# EEM_Connectors.net
KiCad netlist of a schematic drawn in Altium Designer
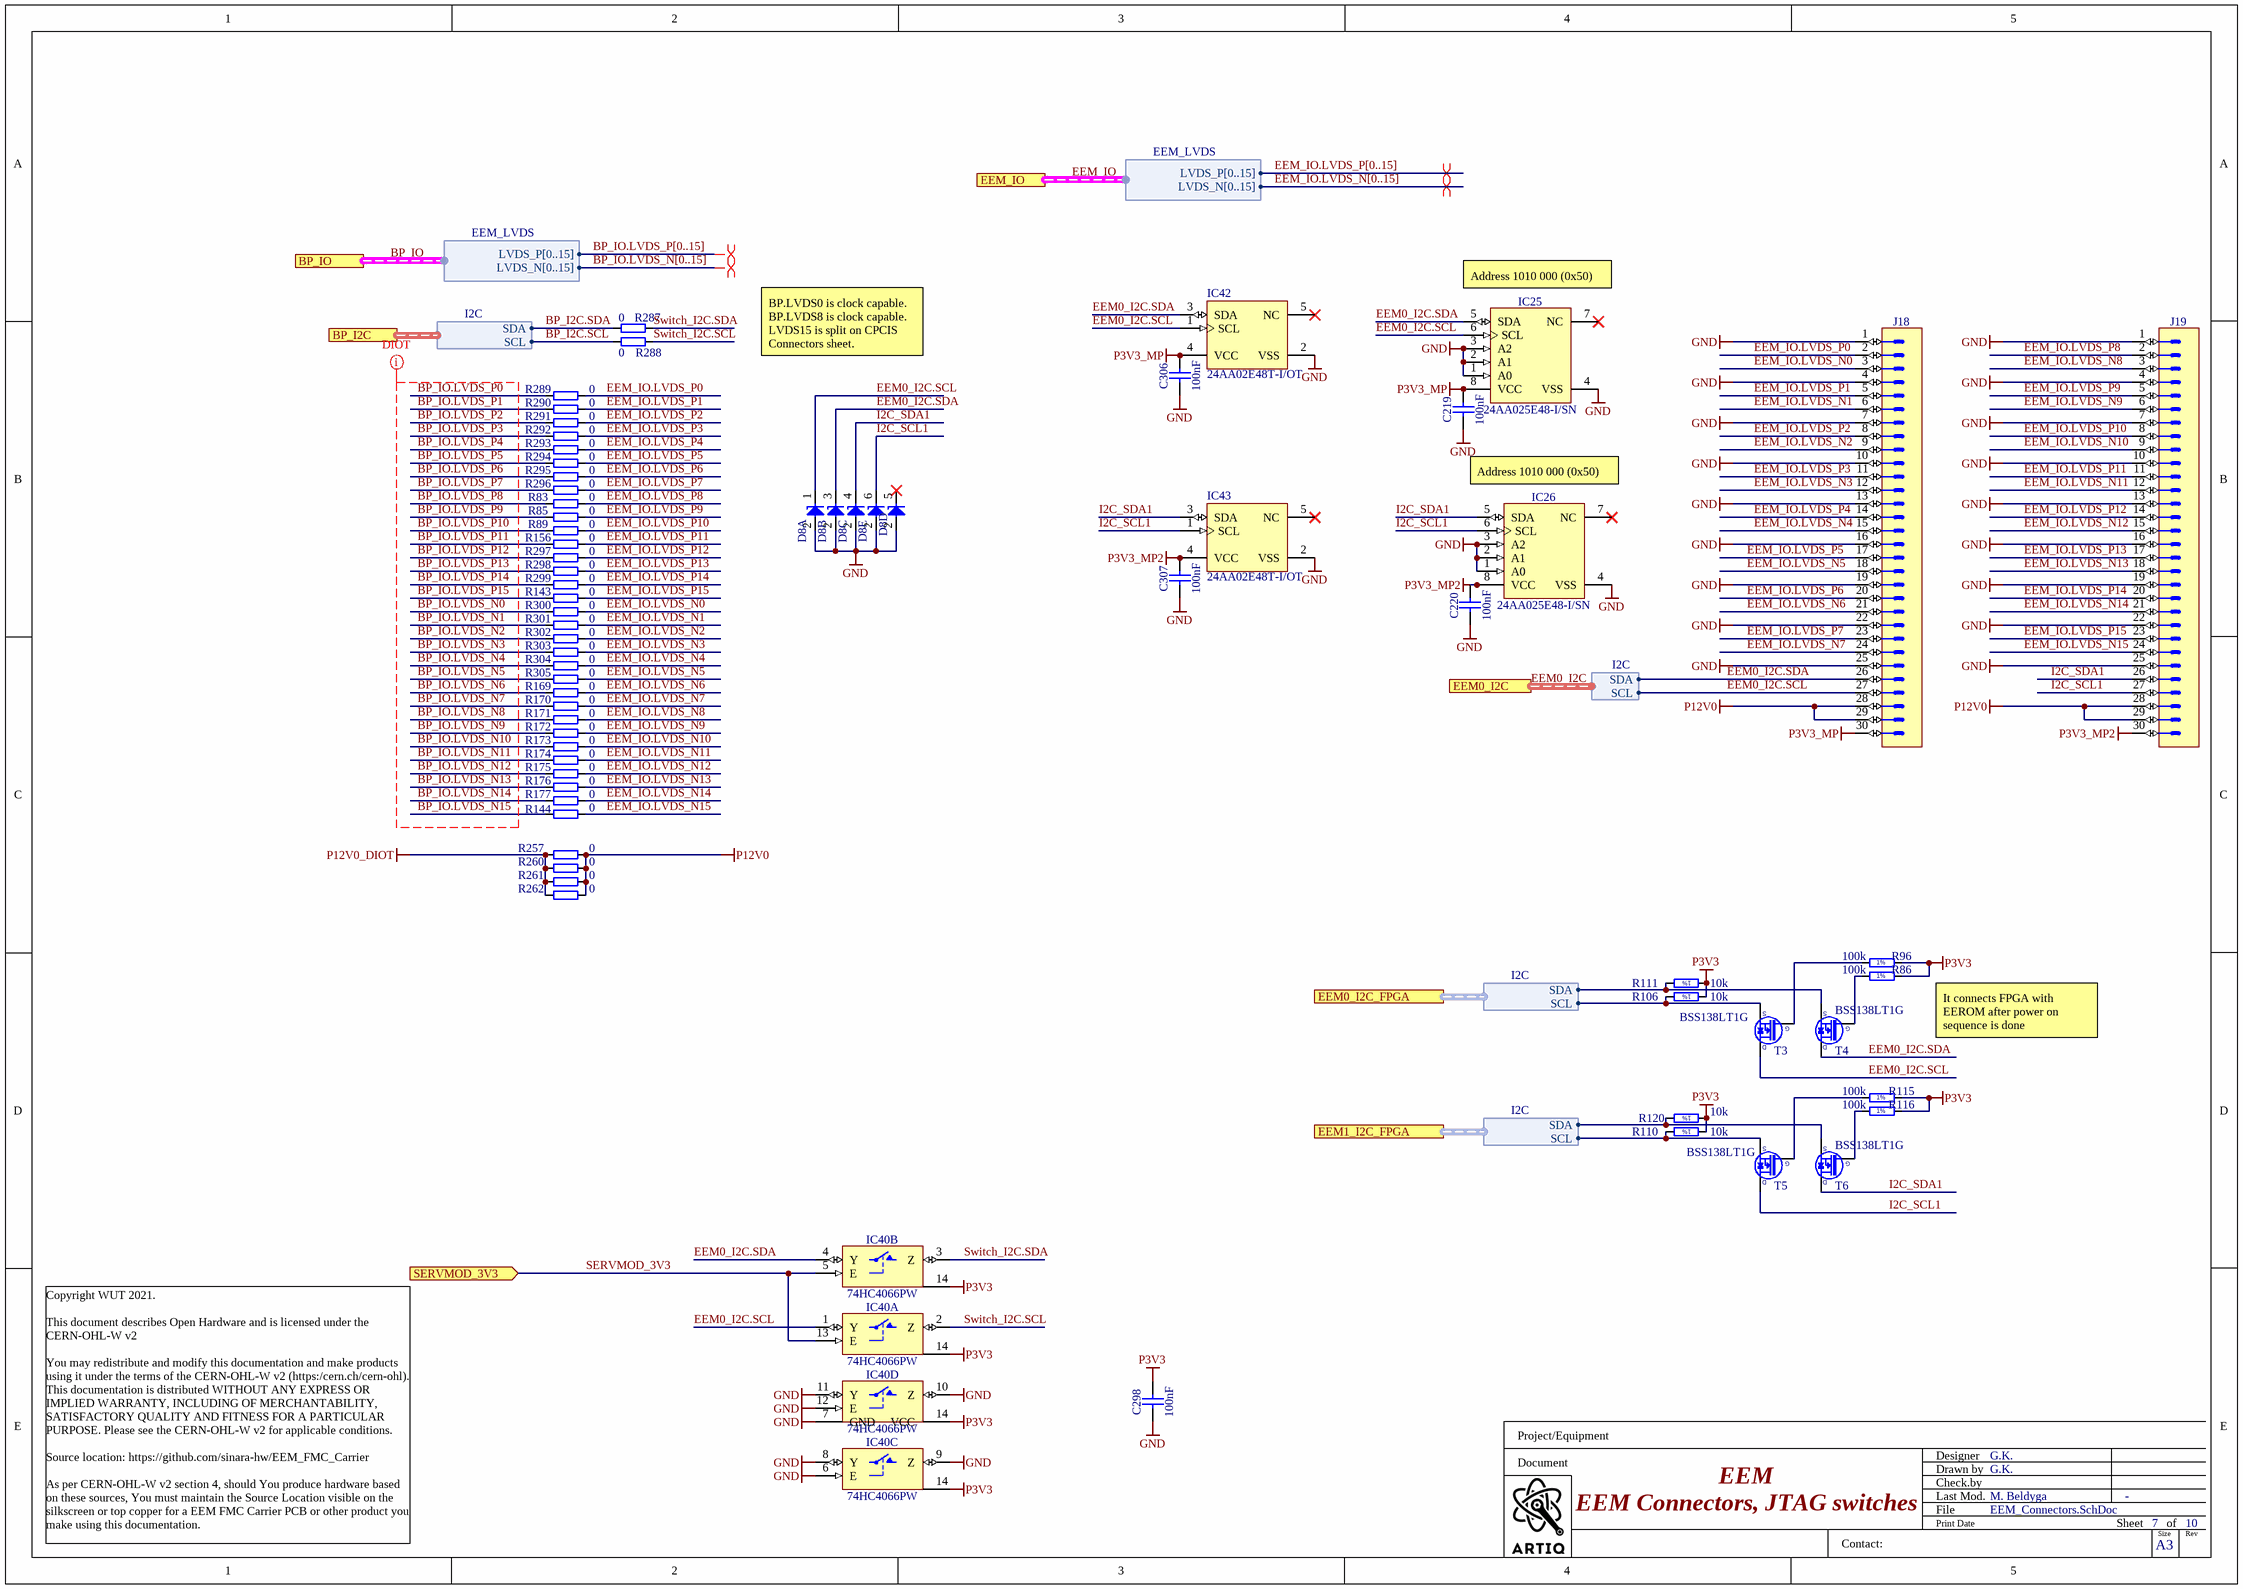
[diagram p0: EEM_Connectors.SchDoc]

(export (version "E")
  (design (tool "Eeschema 10.0.6"))
  (components
    (comp (ref "C219")
      (value "100nF")
      (footprint "CAPC1005X55N")
      (description "Non-polarised capacitor")
      (fields
        (field (name "PART NUMBER") "CC0402_100NF_25V_10%_X7R_YUDEN_TMK105B7104KVHF")
        (field (name "VOLTAGE") "25V")
        (field (name "AUTHOR") "CERN DEM JLC")
      )
      (libsource (lib "Capacitors") (part "Capacitor - non polarized"))
    )
    (comp (ref "C220")
      (value "100nF")
      (footprint "CAPC1005X55N")
      (description "Non-polarised capacitor")
      (fields
        (field (name "PART NUMBER") "CC0402_100NF_16V_10%_X5R")
        (field (name "VOLTAGE") "16V")
        (field (name "AUTHOR") "CERN DEM JLC")
      )
      (libsource (lib "Capacitors") (part "Capacitor - non polarized"))
    )
    (comp (ref "C298")
      (value "100nF")
      (footprint "CAPC1005X55N")
      (description "Non-polarised capacitor")
      (fields
        (field (name "PART NUMBER") "CC0402_100NF_16V_10%_X5R")
        (field (name "VOLTAGE") "16V")
        (field (name "AUTHOR") "CERN DEM JLC")
      )
      (libsource (lib "Capacitors") (part "Capacitor - non polarized"))
    )
    (comp (ref "C306")
      (value "100nF")
      (footprint "CAPC1005X55N")
      (description "Non-polarised capacitor")
      (fields
        (field (name "PART NUMBER") "CC0402_100NF_25V_10%_X7R_YUDEN_TMK105B7104KVHF")
        (field (name "VOLTAGE") "25V")
        (field (name "AUTHOR") "CERN DEM JLC")
      )
      (libsource (lib "Capacitors") (part "Capacitor - non polarized"))
    )
    (comp (ref "C307")
      (value "100nF")
      (footprint "CAPC1005X55N")
      (description "Non-polarised capacitor")
      (fields
        (field (name "PART NUMBER") "CC0402_100NF_25V_10%_X7R_YUDEN_TMK105B7104KVHF")
        (field (name "VOLTAGE") "25V")
        (field (name "AUTHOR") "CERN DEM JLC")
      )
      (libsource (lib "Capacitors") (part "Capacitor - non polarized"))
    )
    (comp (ref "D8")
      (value "PESD3V3L5UY")
      (footprint "SOT65P210X110-6N")
      (description "Fivefold ESD Protection Diode Arrays")
      (fields
        (field (name "VOLTAGE") "3.3V")
        (field (name "POWER") "200W")
        (field (name "AUTHOR") "CERN DEM WB")
      )
      (libsource (lib "ICs And Semiconductors") (part "PESD Array 5diodes 6pins Common anode2"))
    )
    (comp (ref "IC25")
      (value "24AA025E48-I/SN")
      (footprint "SOIC127P600X175-8N")
      (description "1.7V-5.5V, 2K I2C™ Serial EEPROMs with EUI-48™ Node Identity")
      (fields (field (name "MANUFACTURER") "MICROCHIP TECHNOLOGY") (field (name "AUTHOR") "CERN DEM MR"))
      (libsource (lib "ICs And Semiconductors") (part "24AA025E48-I/SN"))
    )
    (comp (ref "IC26")
      (value "24AA025E48-I/SN")
      (footprint "SOIC127P600X175-8N")
      (description "1.7V-5.5V, 2K I2C™ Serial EEPROMs with EUI-48™ Node Identity")
      (fields (field (name "MANUFACTURER") "MICROCHIP TECHNOLOGY") (field (name "AUTHOR") "CERN DEM MR"))
      (libsource (lib "ICs And Semiconductors") (part "24AA025E48-I/SN"))
    )
    (comp (ref "IC40")
      (value "74HC4066PW")
      (footprint "SOP65P640X110-14N")
      (fields (field (name "MANUFACTURER") "NXP SEMICONDUCTORS") (field (name "AUTHOR") "CERN DEM JLC"))
      (libsource (lib "ICs And Semiconductors") (part "4066"))
    )
    (comp (ref "IC42")
      (value "24AA02E48T-I/OT")
      (footprint "SOT95P280X145-5N")
      (description "1.7V-5.5V, 2K I2C Serial EEPROM With EUI-48 Node Identity")
      (fields (field (name "MANUFACTURER") "MICROCHIP TECHNOLOGY") (field (name "AUTHOR") "CERN DEM MR"))
      (libsource (lib "ICs And Semiconductors") (part "24AA02E48T-I/OT"))
    )
    (comp (ref "IC43")
      (value "24AA02E48T-I/OT")
      (footprint "SOT95P280X145-5N")
      (description "1.7V-5.5V, 2K I2C Serial EEPROM With EUI-48 Node Identity")
      (fields (field (name "MANUFACTURER") "MICROCHIP TECHNOLOGY") (field (name "AUTHOR") "CERN DEM MR"))
      (libsource (lib "ICs And Semiconductors") (part "24AA02E48T-I/OT"))
    )
    (comp (ref "J18")
      (value "~")
      (footprint "3M_N2530-6002RB")
      (description "Connector 30 Male")
      (fields
        (field (name "PART NUMBER") "3M_N2530-6002RB")
        (field (name "MANUFACTURER") "3M")
        (field (name "AUTHOR") "CERN DEM JLC")
      )
      (libsource (lib "Connectors") (part "Connector 30 Male"))
    )
    (comp (ref "J19")
      (value "~")
      (footprint "3M_N2530-6002RB")
      (description "Connector 30 Male")
      (fields
        (field (name "PART NUMBER") "3M_N2530-6002RB")
        (field (name "MANUFACTURER") "3M")
        (field (name "AUTHOR") "CERN DEM JLC")
      )
      (libsource (lib "Connectors") (part "Connector 30 Male"))
    )
    (comp (ref "R83")
      (value "0")
      (footprint "RESC1005X40N")
      (description "Resistor")
      (fields
        (field (name "PART NUMBER") "R0402_0R_JUMPER")
        (field (name "MANUFACTURER") "GENERIC")
        (field (name "AUTHOR") "CERN DEM JLC")
      )
      (libsource (lib "Resistors") (part "Resistor"))
    )
    (comp (ref "R85")
      (value "0")
      (footprint "RESC1005X40N")
      (description "Resistor")
      (fields
        (field (name "PART NUMBER") "R0402_0R_JUMPER")
        (field (name "MANUFACTURER") "GENERIC")
        (field (name "AUTHOR") "CERN DEM JLC")
      )
      (libsource (lib "Resistors") (part "Resistor"))
    )
    (comp (ref "R86")
      (value "100k")
      (footprint "RESC1005X40N")
      (description "Resistor - 1%")
      (fields
        (field (name "PART NUMBER") "R0402_100K_1%_0.0625W_100PPM")
        (field (name "POWER") "0.0625W")
        (field (name "AUTHOR") "CERN DEM JLC")
      )
      (libsource (lib "Resistors") (part "Resistor - 1%"))
    )
    (comp (ref "R89")
      (value "0")
      (footprint "RESC1005X40N")
      (description "Resistor")
      (fields
        (field (name "PART NUMBER") "R0402_0R_JUMPER")
        (field (name "MANUFACTURER") "GENERIC")
        (field (name "AUTHOR") "CERN DEM JLC")
      )
      (libsource (lib "Resistors") (part "Resistor"))
    )
    (comp (ref "R96")
      (value "100k")
      (footprint "RESC1005X40N")
      (description "Resistor - 1%")
      (fields
        (field (name "PART NUMBER") "R0402_100K_1%_0.0625W_100PPM")
        (field (name "POWER") "0.0625W")
        (field (name "AUTHOR") "CERN DEM JLC")
      )
      (libsource (lib "Resistors") (part "Resistor - 1%"))
    )
    (comp (ref "R106")
      (value "10k")
      (footprint "RESC1005X40N")
      (description "Resistor - 1%")
      (fields
        (field (name "PART NUMBER") "R0402_10K_1%_0.0625W_100PPM")
        (field (name "POWER") "0.0625W")
        (field (name "AUTHOR") "CERN DEM JLC")
      )
      (libsource (lib "Resistors") (part "Resistor - 1%"))
    )
    (comp (ref "R110")
      (value "10k")
      (footprint "RESC1005X40N")
      (description "Resistor - 1%")
      (fields
        (field (name "PART NUMBER") "R0402_10K_1%_0.0625W_100PPM")
        (field (name "POWER") "0.0625W")
        (field (name "AUTHOR") "CERN DEM JLC")
      )
      (libsource (lib "Resistors") (part "Resistor - 1%"))
    )
    (comp (ref "R111")
      (value "10k")
      (footprint "RESC1005X40N")
      (description "Resistor - 1%")
      (fields
        (field (name "PART NUMBER") "R0402_10K_1%_0.0625W_100PPM")
        (field (name "POWER") "0.0625W")
        (field (name "AUTHOR") "CERN DEM JLC")
      )
      (libsource (lib "Resistors") (part "Resistor - 1%"))
    )
    (comp (ref "R115")
      (value "100k")
      (footprint "RESC1005X40N")
      (description "Resistor - 1%")
      (fields
        (field (name "PART NUMBER") "R0402_100K_1%_0.0625W_100PPM")
        (field (name "POWER") "0.0625W")
        (field (name "AUTHOR") "CERN DEM JLC")
      )
      (libsource (lib "Resistors") (part "Resistor - 1%"))
    )
    (comp (ref "R116")
      (value "100k")
      (footprint "RESC1005X40N")
      (description "Resistor - 1%")
      (fields
        (field (name "PART NUMBER") "R0402_100K_1%_0.0625W_100PPM")
        (field (name "POWER") "0.0625W")
        (field (name "AUTHOR") "CERN DEM JLC")
      )
      (libsource (lib "Resistors") (part "Resistor - 1%"))
    )
    (comp (ref "R120")
      (value "10k")
      (footprint "RESC1005X40N")
      (description "Resistor - 1%")
      (fields
        (field (name "PART NUMBER") "R0402_10K_1%_0.0625W_100PPM")
        (field (name "POWER") "0.0625W")
        (field (name "AUTHOR") "CERN DEM JLC")
      )
      (libsource (lib "Resistors") (part "Resistor - 1%"))
    )
    (comp (ref "R143")
      (value "0")
      (footprint "RESC1005X40N")
      (description "Resistor")
      (fields
        (field (name "PART NUMBER") "R0402_0R_JUMPER")
        (field (name "MANUFACTURER") "GENERIC")
        (field (name "AUTHOR") "CERN DEM JLC")
      )
      (libsource (lib "Resistors") (part "Resistor"))
    )
    (comp (ref "R144")
      (value "0")
      (footprint "RESC1005X40N")
      (description "Resistor")
      (fields
        (field (name "PART NUMBER") "R0402_0R_JUMPER")
        (field (name "MANUFACTURER") "GENERIC")
        (field (name "AUTHOR") "CERN DEM JLC")
      )
      (libsource (lib "Resistors") (part "Resistor"))
    )
    (comp (ref "R156")
      (value "0")
      (footprint "RESC1005X40N")
      (description "Resistor")
      (fields
        (field (name "PART NUMBER") "R0402_0R_JUMPER")
        (field (name "MANUFACTURER") "GENERIC")
        (field (name "AUTHOR") "CERN DEM JLC")
      )
      (libsource (lib "Resistors") (part "Resistor"))
    )
    (comp (ref "R169")
      (value "0")
      (footprint "RESC1005X40N")
      (description "Resistor")
      (fields
        (field (name "PART NUMBER") "R0402_0R_JUMPER")
        (field (name "MANUFACTURER") "GENERIC")
        (field (name "AUTHOR") "CERN DEM JLC")
      )
      (libsource (lib "Resistors") (part "Resistor"))
    )
    (comp (ref "R170")
      (value "0")
      (footprint "RESC1005X40N")
      (description "Resistor")
      (fields
        (field (name "PART NUMBER") "R0402_0R_JUMPER")
        (field (name "MANUFACTURER") "GENERIC")
        (field (name "AUTHOR") "CERN DEM JLC")
      )
      (libsource (lib "Resistors") (part "Resistor"))
    )
    (comp (ref "R171")
      (value "0")
      (footprint "RESC1005X40N")
      (description "Resistor")
      (fields
        (field (name "PART NUMBER") "R0402_0R_JUMPER")
        (field (name "MANUFACTURER") "GENERIC")
        (field (name "AUTHOR") "CERN DEM JLC")
      )
      (libsource (lib "Resistors") (part "Resistor"))
    )
    (comp (ref "R172")
      (value "0")
      (footprint "RESC1005X40N")
      (description "Resistor")
      (fields
        (field (name "PART NUMBER") "R0402_0R_JUMPER")
        (field (name "MANUFACTURER") "GENERIC")
        (field (name "AUTHOR") "CERN DEM JLC")
      )
      (libsource (lib "Resistors") (part "Resistor"))
    )
    (comp (ref "R173")
      (value "0")
      (footprint "RESC1005X40N")
      (description "Resistor")
      (fields
        (field (name "PART NUMBER") "R0402_0R_JUMPER")
        (field (name "MANUFACTURER") "GENERIC")
        (field (name "AUTHOR") "CERN DEM JLC")
      )
      (libsource (lib "Resistors") (part "Resistor"))
    )
    (comp (ref "R174")
      (value "0")
      (footprint "RESC1005X40N")
      (description "Resistor")
      (fields
        (field (name "PART NUMBER") "R0402_0R_JUMPER")
        (field (name "MANUFACTURER") "GENERIC")
        (field (name "AUTHOR") "CERN DEM JLC")
      )
      (libsource (lib "Resistors") (part "Resistor"))
    )
    (comp (ref "R175")
      (value "0")
      (footprint "RESC1005X40N")
      (description "Resistor")
      (fields
        (field (name "PART NUMBER") "R0402_0R_JUMPER")
        (field (name "MANUFACTURER") "GENERIC")
        (field (name "AUTHOR") "CERN DEM JLC")
      )
      (libsource (lib "Resistors") (part "Resistor"))
    )
    (comp (ref "R176")
      (value "0")
      (footprint "RESC1005X40N")
      (description "Resistor")
      (fields
        (field (name "PART NUMBER") "R0402_0R_JUMPER")
        (field (name "MANUFACTURER") "GENERIC")
        (field (name "AUTHOR") "CERN DEM JLC")
      )
      (libsource (lib "Resistors") (part "Resistor"))
    )
    (comp (ref "R177")
      (value "0")
      (footprint "RESC1005X40N")
      (description "Resistor")
      (fields
        (field (name "PART NUMBER") "R0402_0R_JUMPER")
        (field (name "MANUFACTURER") "GENERIC")
        (field (name "AUTHOR") "CERN DEM JLC")
      )
      (libsource (lib "Resistors") (part "Resistor"))
    )
    (comp (ref "R257")
      (value "0")
      (footprint "RESC1005X40N")
      (description "Resistor")
      (fields
        (field (name "PART NUMBER") "R0402_0R_JUMPER")
        (field (name "MANUFACTURER") "GENERIC")
        (field (name "AUTHOR") "CERN DEM JLC")
      )
      (libsource (lib "Resistors") (part "Resistor"))
    )
    (comp (ref "R260")
      (value "0")
      (footprint "RESC1005X40N")
      (description "Resistor")
      (fields
        (field (name "PART NUMBER") "R0402_0R_JUMPER")
        (field (name "MANUFACTURER") "GENERIC")
        (field (name "AUTHOR") "CERN DEM JLC")
      )
      (libsource (lib "Resistors") (part "Resistor"))
    )
    (comp (ref "R261")
      (value "0")
      (footprint "RESC1005X40N")
      (description "Resistor")
      (fields
        (field (name "PART NUMBER") "R0402_0R_JUMPER")
        (field (name "MANUFACTURER") "GENERIC")
        (field (name "AUTHOR") "CERN DEM JLC")
      )
      (libsource (lib "Resistors") (part "Resistor"))
    )
    (comp (ref "R262")
      (value "0")
      (footprint "RESC1005X40N")
      (description "Resistor")
      (fields
        (field (name "PART NUMBER") "R0402_0R_JUMPER")
        (field (name "MANUFACTURER") "GENERIC")
        (field (name "AUTHOR") "CERN DEM JLC")
      )
      (libsource (lib "Resistors") (part "Resistor"))
    )
    (comp (ref "R287")
      (value "0")
      (footprint "RESC1005X40N")
      (description "Resistor")
      (fields
        (field (name "PART NUMBER") "R0402_0R_JUMPER")
        (field (name "MANUFACTURER") "GENERIC")
        (field (name "AUTHOR") "CERN DEM JLC")
      )
      (libsource (lib "Resistors") (part "Resistor"))
    )
    (comp (ref "R288")
      (value "0")
      (footprint "RESC1005X40N")
      (description "Resistor")
      (fields
        (field (name "PART NUMBER") "R0402_0R_JUMPER")
        (field (name "MANUFACTURER") "GENERIC")
        (field (name "AUTHOR") "CERN DEM JLC")
      )
      (libsource (lib "Resistors") (part "Resistor"))
    )
    (comp (ref "R289")
      (value "0")
      (footprint "RESC1005X40N")
      (description "Resistor")
      (fields
        (field (name "PART NUMBER") "R0402_0R_JUMPER")
        (field (name "MANUFACTURER") "GENERIC")
        (field (name "AUTHOR") "CERN DEM JLC")
      )
      (libsource (lib "Resistors") (part "Resistor"))
    )
    (comp (ref "R290")
      (value "0")
      (footprint "RESC1005X40N")
      (description "Resistor")
      (fields
        (field (name "PART NUMBER") "R0402_0R_JUMPER")
        (field (name "MANUFACTURER") "GENERIC")
        (field (name "AUTHOR") "CERN DEM JLC")
      )
      (libsource (lib "Resistors") (part "Resistor"))
    )
    (comp (ref "R291")
      (value "0")
      (footprint "RESC1005X40N")
      (description "Resistor")
      (fields
        (field (name "PART NUMBER") "R0402_0R_JUMPER")
        (field (name "MANUFACTURER") "GENERIC")
        (field (name "AUTHOR") "CERN DEM JLC")
      )
      (libsource (lib "Resistors") (part "Resistor"))
    )
    (comp (ref "R292")
      (value "0")
      (footprint "RESC1005X40N")
      (description "Resistor")
      (fields
        (field (name "PART NUMBER") "R0402_0R_JUMPER")
        (field (name "MANUFACTURER") "GENERIC")
        (field (name "AUTHOR") "CERN DEM JLC")
      )
      (libsource (lib "Resistors") (part "Resistor"))
    )
    (comp (ref "R293")
      (value "0")
      (footprint "RESC1005X40N")
      (description "Resistor")
      (fields
        (field (name "PART NUMBER") "R0402_0R_JUMPER")
        (field (name "MANUFACTURER") "GENERIC")
        (field (name "AUTHOR") "CERN DEM JLC")
      )
      (libsource (lib "Resistors") (part "Resistor"))
    )
    (comp (ref "R294")
      (value "0")
      (footprint "RESC1005X40N")
      (description "Resistor")
      (fields
        (field (name "PART NUMBER") "R0402_0R_JUMPER")
        (field (name "MANUFACTURER") "GENERIC")
        (field (name "AUTHOR") "CERN DEM JLC")
      )
      (libsource (lib "Resistors") (part "Resistor"))
    )
    (comp (ref "R295")
      (value "0")
      (footprint "RESC1005X40N")
      (description "Resistor")
      (fields
        (field (name "PART NUMBER") "R0402_0R_JUMPER")
        (field (name "MANUFACTURER") "GENERIC")
        (field (name "AUTHOR") "CERN DEM JLC")
      )
      (libsource (lib "Resistors") (part "Resistor"))
    )
    (comp (ref "R296")
      (value "0")
      (footprint "RESC1005X40N")
      (description "Resistor")
      (fields
        (field (name "PART NUMBER") "R0402_0R_JUMPER")
        (field (name "MANUFACTURER") "GENERIC")
        (field (name "AUTHOR") "CERN DEM JLC")
      )
      (libsource (lib "Resistors") (part "Resistor"))
    )
    (comp (ref "R297")
      (value "0")
      (footprint "RESC1005X40N")
      (description "Resistor")
      (fields
        (field (name "PART NUMBER") "R0402_0R_JUMPER")
        (field (name "MANUFACTURER") "GENERIC")
        (field (name "AUTHOR") "CERN DEM JLC")
      )
      (libsource (lib "Resistors") (part "Resistor"))
    )
    (comp (ref "R298")
      (value "0")
      (footprint "RESC1005X40N")
      (description "Resistor")
      (fields
        (field (name "PART NUMBER") "R0402_0R_JUMPER")
        (field (name "MANUFACTURER") "GENERIC")
        (field (name "AUTHOR") "CERN DEM JLC")
      )
      (libsource (lib "Resistors") (part "Resistor"))
    )
    (comp (ref "R299")
      (value "0")
      (footprint "RESC1005X40N")
      (description "Resistor")
      (fields
        (field (name "PART NUMBER") "R0402_0R_JUMPER")
        (field (name "MANUFACTURER") "GENERIC")
        (field (name "AUTHOR") "CERN DEM JLC")
      )
      (libsource (lib "Resistors") (part "Resistor"))
    )
    (comp (ref "R300")
      (value "0")
      (footprint "RESC1005X40N")
      (description "Resistor")
      (fields
        (field (name "PART NUMBER") "R0402_0R_JUMPER")
        (field (name "MANUFACTURER") "GENERIC")
        (field (name "AUTHOR") "CERN DEM JLC")
      )
      (libsource (lib "Resistors") (part "Resistor"))
    )
    (comp (ref "R301")
      (value "0")
      (footprint "RESC1005X40N")
      (description "Resistor")
      (fields
        (field (name "PART NUMBER") "R0402_0R_JUMPER")
        (field (name "MANUFACTURER") "GENERIC")
        (field (name "AUTHOR") "CERN DEM JLC")
      )
      (libsource (lib "Resistors") (part "Resistor"))
    )
    (comp (ref "R302")
      (value "0")
      (footprint "RESC1005X40N")
      (description "Resistor")
      (fields
        (field (name "PART NUMBER") "R0402_0R_JUMPER")
        (field (name "MANUFACTURER") "GENERIC")
        (field (name "AUTHOR") "CERN DEM JLC")
      )
      (libsource (lib "Resistors") (part "Resistor"))
    )
    (comp (ref "R303")
      (value "0")
      (footprint "RESC1005X40N")
      (description "Resistor")
      (fields
        (field (name "PART NUMBER") "R0402_0R_JUMPER")
        (field (name "MANUFACTURER") "GENERIC")
        (field (name "AUTHOR") "CERN DEM JLC")
      )
      (libsource (lib "Resistors") (part "Resistor"))
    )
    (comp (ref "R304")
      (value "0")
      (footprint "RESC1005X40N")
      (description "Resistor")
      (fields
        (field (name "PART NUMBER") "R0402_0R_JUMPER")
        (field (name "MANUFACTURER") "GENERIC")
        (field (name "AUTHOR") "CERN DEM JLC")
      )
      (libsource (lib "Resistors") (part "Resistor"))
    )
    (comp (ref "R305")
      (value "0")
      (footprint "RESC1005X40N")
      (description "Resistor")
      (fields
        (field (name "PART NUMBER") "R0402_0R_JUMPER")
        (field (name "MANUFACTURER") "GENERIC")
        (field (name "AUTHOR") "CERN DEM JLC")
      )
      (libsource (lib "Resistors") (part "Resistor"))
    )
    (comp (ref "T3")
      (value "BSS138LT1G")
      (footprint "SOT95P240X110-3N")
      (description "N-CHANNEL MOSFET WITH DIODE")
      (fields (field (name "MANUFACTURER") "ON SEMICONDUCTOR") (field (name "AUTHOR") "CERN DEM JLC"))
      (libsource (lib "ICs And Semiconductors") (part "N-MOSFET-D 1G 2S 3D"))
    )
    (comp (ref "T4")
      (value "BSS138LT1G")
      (footprint "SOT95P240X110-3N")
      (description "N-CHANNEL MOSFET WITH DIODE")
      (fields (field (name "MANUFACTURER") "ON SEMICONDUCTOR") (field (name "AUTHOR") "CERN DEM JLC"))
      (libsource (lib "ICs And Semiconductors") (part "N-MOSFET-D 1G 2S 3D"))
    )
    (comp (ref "T5")
      (value "BSS138LT1G")
      (footprint "SOT95P240X110-3N")
      (description "N-CHANNEL MOSFET WITH DIODE")
      (fields (field (name "MANUFACTURER") "ON SEMICONDUCTOR") (field (name "AUTHOR") "CERN DEM JLC"))
      (libsource (lib "ICs And Semiconductors") (part "N-MOSFET-D 1G 2S 3D"))
    )
    (comp (ref "T6")
      (value "BSS138LT1G")
      (footprint "SOT95P240X110-3N")
      (description "N-CHANNEL MOSFET WITH DIODE")
      (fields (field (name "MANUFACTURER") "ON SEMICONDUCTOR") (field (name "AUTHOR") "CERN DEM JLC"))
      (libsource (lib "ICs And Semiconductors") (part "N-MOSFET-D 1G 2S 3D"))
    )
  )
  (nets
    (net (code "5") (name "/BP_I2C.SCL") (class "Default")
      (node (ref "R288") (pin "1") (pinfunction "1_1") (pintype "passive"))
    )
    (net (code "6") (name "/BP_I2C.SDA") (class "Default")
      (node (ref "R287") (pin "1") (pinfunction "1_1") (pintype "passive"))
    )
    (net (code "7") (name "/BP_IO.LVDS_N0") (class "Default")
      (node (ref "R300") (pin "1") (pinfunction "1_1") (pintype "passive"))
    )
    (net (code "8") (name "/BP_IO.LVDS_N1") (class "Default")
      (node (ref "R301") (pin "1") (pinfunction "1_1") (pintype "passive"))
    )
    (net (code "9") (name "/BP_IO.LVDS_N2") (class "Default")
      (node (ref "R302") (pin "1") (pinfunction "1_1") (pintype "passive"))
    )
    (net (code "10") (name "/BP_IO.LVDS_N3") (class "Default")
      (node (ref "R303") (pin "1") (pinfunction "1_1") (pintype "passive"))
    )
    (net (code "11") (name "/BP_IO.LVDS_N4") (class "Default")
      (node (ref "R304") (pin "1") (pinfunction "1_1") (pintype "passive"))
    )
    (net (code "12") (name "/BP_IO.LVDS_N5") (class "Default")
      (node (ref "R305") (pin "1") (pinfunction "1_1") (pintype "passive"))
    )
    (net (code "13") (name "/BP_IO.LVDS_N6") (class "Default")
      (node (ref "R169") (pin "1") (pinfunction "1_1") (pintype "passive"))
    )
    (net (code "14") (name "/BP_IO.LVDS_N7") (class "Default")
      (node (ref "R170") (pin "1") (pinfunction "1_1") (pintype "passive"))
    )
    (net (code "15") (name "/BP_IO.LVDS_N8") (class "Default")
      (node (ref "R171") (pin "1") (pinfunction "1_1") (pintype "passive"))
    )
    (net (code "16") (name "/BP_IO.LVDS_N9") (class "Default")
      (node (ref "R172") (pin "1") (pinfunction "1_1") (pintype "passive"))
    )
    (net (code "17") (name "/BP_IO.LVDS_N10") (class "Default")
      (node (ref "R173") (pin "1") (pinfunction "1_1") (pintype "passive"))
    )
    (net (code "18") (name "/BP_IO.LVDS_N11") (class "Default")
      (node (ref "R174") (pin "1") (pinfunction "1_1") (pintype "passive"))
    )
    (net (code "19") (name "/BP_IO.LVDS_N12") (class "Default")
      (node (ref "R175") (pin "1") (pinfunction "1_1") (pintype "passive"))
    )
    (net (code "20") (name "/BP_IO.LVDS_N13") (class "Default")
      (node (ref "R176") (pin "1") (pinfunction "1_1") (pintype "passive"))
    )
    (net (code "21") (name "/BP_IO.LVDS_N14") (class "Default")
      (node (ref "R177") (pin "1") (pinfunction "1_1") (pintype "passive"))
    )
    (net (code "22") (name "/BP_IO.LVDS_N15") (class "Default")
      (node (ref "R144") (pin "1") (pinfunction "1_1") (pintype "passive"))
    )
    (net (code "24") (name "/BP_IO.LVDS_P0") (class "Default")
      (node (ref "R289") (pin "1") (pinfunction "1_1") (pintype "passive"))
    )
    (net (code "25") (name "/BP_IO.LVDS_P1") (class "Default")
      (node (ref "R290") (pin "1") (pinfunction "1_1") (pintype "passive"))
    )
    (net (code "26") (name "/BP_IO.LVDS_P2") (class "Default")
      (node (ref "R291") (pin "1") (pinfunction "1_1") (pintype "passive"))
    )
    (net (code "27") (name "/BP_IO.LVDS_P3") (class "Default")
      (node (ref "R292") (pin "1") (pinfunction "1_1") (pintype "passive"))
    )
    (net (code "28") (name "/BP_IO.LVDS_P4") (class "Default")
      (node (ref "R293") (pin "1") (pinfunction "1_1") (pintype "passive"))
    )
    (net (code "29") (name "/BP_IO.LVDS_P5") (class "Default")
      (node (ref "R294") (pin "1") (pinfunction "1_1") (pintype "passive"))
    )
    (net (code "30") (name "/BP_IO.LVDS_P6") (class "Default")
      (node (ref "R295") (pin "1") (pinfunction "1_1") (pintype "passive"))
    )
    (net (code "31") (name "/BP_IO.LVDS_P7") (class "Default")
      (node (ref "R296") (pin "1") (pinfunction "1_1") (pintype "passive"))
    )
    (net (code "32") (name "/BP_IO.LVDS_P8") (class "Default")
      (node (ref "R83") (pin "1") (pinfunction "1_1") (pintype "passive"))
    )
    (net (code "33") (name "/BP_IO.LVDS_P9") (class "Default")
      (node (ref "R85") (pin "1") (pinfunction "1_1") (pintype "passive"))
    )
    (net (code "34") (name "/BP_IO.LVDS_P10") (class "Default")
      (node (ref "R89") (pin "1") (pinfunction "1_1") (pintype "passive"))
    )
    (net (code "35") (name "/BP_IO.LVDS_P11") (class "Default")
      (node (ref "R156") (pin "1") (pinfunction "1_1") (pintype "passive"))
    )
    (net (code "36") (name "/BP_IO.LVDS_P12") (class "Default")
      (node (ref "R297") (pin "1") (pinfunction "1_1") (pintype "passive"))
    )
    (net (code "37") (name "/BP_IO.LVDS_P13") (class "Default")
      (node (ref "R298") (pin "1") (pinfunction "1_1") (pintype "passive"))
    )
    (net (code "38") (name "/BP_IO.LVDS_P14") (class "Default")
      (node (ref "R299") (pin "1") (pinfunction "1_1") (pintype "passive"))
    )
    (net (code "39") (name "/BP_IO.LVDS_P15") (class "Default")
      (node (ref "R143") (pin "1") (pinfunction "1_1") (pintype "passive"))
    )
    (net (code "42") (name "/EEM0_I2C.SCL") (class "Default")
      (node (ref "D8") (pin "1") (pinfunction "C_1") (pintype "passive"))
      (node (ref "IC25") (pin "6") (pinfunction "SCL_6") (pintype "input"))
      (node (ref "IC40") (pin "1") (pinfunction "Y_1") (pintype "bidirectional"))
      (node (ref "IC42") (pin "1") (pinfunction "SCL_1") (pintype "input"))
      (node (ref "J18") (pin "27") (pinfunction "27_27") (pintype "bidirectional"))
      (node (ref "T3") (pin "3") (pinfunction "D_3") (pintype "passive"))
    )
    (net (code "43") (name "/EEM0_I2C.SDA") (class "Default")
      (node (ref "D8") (pin "3") (pinfunction "C_3") (pintype "passive"))
      (node (ref "IC25") (pin "5") (pinfunction "SDA_5") (pintype "bidirectional"))
      (node (ref "IC40") (pin "4") (pinfunction "Y_4") (pintype "bidirectional"))
      (node (ref "IC42") (pin "3") (pinfunction "SDA_3") (pintype "bidirectional"))
      (node (ref "J18") (pin "26") (pinfunction "26_26") (pintype "bidirectional"))
      (node (ref "T4") (pin "3") (pinfunction "D_3") (pintype "passive"))
    )
    (net (code "45") (name "/EEM_IO.LVDS_N0") (class "Default")
      (node (ref "J18") (pin "3") (pinfunction "3_3") (pintype "bidirectional"))
      (node (ref "R300") (pin "2") (pinfunction "2_2") (pintype "passive"))
    )
    (net (code "46") (name "/EEM_IO.LVDS_N1") (class "Default")
      (node (ref "J18") (pin "6") (pinfunction "6_6") (pintype "bidirectional"))
      (node (ref "R301") (pin "2") (pinfunction "2_2") (pintype "passive"))
    )
    (net (code "47") (name "/EEM_IO.LVDS_N2") (class "Default")
      (node (ref "J18") (pin "9") (pinfunction "9_9") (pintype "bidirectional"))
      (node (ref "R302") (pin "2") (pinfunction "2_2") (pintype "passive"))
    )
    (net (code "48") (name "/EEM_IO.LVDS_N3") (class "Default")
      (node (ref "J18") (pin "12") (pinfunction "12_12") (pintype "bidirectional"))
      (node (ref "R303") (pin "2") (pinfunction "2_2") (pintype "passive"))
    )
    (net (code "49") (name "/EEM_IO.LVDS_N4") (class "Default")
      (node (ref "J18") (pin "15") (pinfunction "15_15") (pintype "bidirectional"))
      (node (ref "R304") (pin "2") (pinfunction "2_2") (pintype "passive"))
    )
    (net (code "50") (name "/EEM_IO.LVDS_N5") (class "Default")
      (node (ref "J18") (pin "18") (pinfunction "18_18") (pintype "bidirectional"))
      (node (ref "R305") (pin "2") (pinfunction "2_2") (pintype "passive"))
    )
    (net (code "51") (name "/EEM_IO.LVDS_N6") (class "Default")
      (node (ref "J18") (pin "21") (pinfunction "21_21") (pintype "bidirectional"))
      (node (ref "R169") (pin "2") (pinfunction "2_2") (pintype "passive"))
    )
    (net (code "52") (name "/EEM_IO.LVDS_N7") (class "Default")
      (node (ref "J18") (pin "24") (pinfunction "24_24") (pintype "bidirectional"))
      (node (ref "R170") (pin "2") (pinfunction "2_2") (pintype "passive"))
    )
    (net (code "53") (name "/EEM_IO.LVDS_N8") (class "Default")
      (node (ref "J19") (pin "3") (pinfunction "3_3") (pintype "bidirectional"))
      (node (ref "R171") (pin "2") (pinfunction "2_2") (pintype "passive"))
    )
    (net (code "54") (name "/EEM_IO.LVDS_N9") (class "Default")
      (node (ref "J19") (pin "6") (pinfunction "6_6") (pintype "bidirectional"))
      (node (ref "R172") (pin "2") (pinfunction "2_2") (pintype "passive"))
    )
    (net (code "55") (name "/EEM_IO.LVDS_N10") (class "Default")
      (node (ref "J19") (pin "9") (pinfunction "9_9") (pintype "bidirectional"))
      (node (ref "R173") (pin "2") (pinfunction "2_2") (pintype "passive"))
    )
    (net (code "56") (name "/EEM_IO.LVDS_N11") (class "Default")
      (node (ref "J19") (pin "12") (pinfunction "12_12") (pintype "bidirectional"))
      (node (ref "R174") (pin "2") (pinfunction "2_2") (pintype "passive"))
    )
    (net (code "57") (name "/EEM_IO.LVDS_N12") (class "Default")
      (node (ref "J19") (pin "15") (pinfunction "15_15") (pintype "bidirectional"))
      (node (ref "R175") (pin "2") (pinfunction "2_2") (pintype "passive"))
    )
    (net (code "58") (name "/EEM_IO.LVDS_N13") (class "Default")
      (node (ref "J19") (pin "18") (pinfunction "18_18") (pintype "bidirectional"))
      (node (ref "R176") (pin "2") (pinfunction "2_2") (pintype "passive"))
    )
    (net (code "59") (name "/EEM_IO.LVDS_N14") (class "Default")
      (node (ref "J19") (pin "21") (pinfunction "21_21") (pintype "bidirectional"))
      (node (ref "R177") (pin "2") (pinfunction "2_2") (pintype "passive"))
    )
    (net (code "60") (name "/EEM_IO.LVDS_N15") (class "Default")
      (node (ref "J19") (pin "24") (pinfunction "24_24") (pintype "bidirectional"))
      (node (ref "R144") (pin "2") (pinfunction "2_2") (pintype "passive"))
    )
    (net (code "62") (name "/EEM_IO.LVDS_P0") (class "Default")
      (node (ref "J18") (pin "2") (pinfunction "2_2") (pintype "bidirectional"))
      (node (ref "R289") (pin "2") (pinfunction "2_2") (pintype "passive"))
    )
    (net (code "63") (name "/EEM_IO.LVDS_P1") (class "Default")
      (node (ref "J18") (pin "5") (pinfunction "5_5") (pintype "bidirectional"))
      (node (ref "R290") (pin "2") (pinfunction "2_2") (pintype "passive"))
    )
    (net (code "64") (name "/EEM_IO.LVDS_P2") (class "Default")
      (node (ref "J18") (pin "8") (pinfunction "8_8") (pintype "bidirectional"))
      (node (ref "R291") (pin "2") (pinfunction "2_2") (pintype "passive"))
    )
    (net (code "65") (name "/EEM_IO.LVDS_P3") (class "Default")
      (node (ref "J18") (pin "11") (pinfunction "11_11") (pintype "bidirectional"))
      (node (ref "R292") (pin "2") (pinfunction "2_2") (pintype "passive"))
    )
    (net (code "66") (name "/EEM_IO.LVDS_P4") (class "Default")
      (node (ref "J18") (pin "14") (pinfunction "14_14") (pintype "bidirectional"))
      (node (ref "R293") (pin "2") (pinfunction "2_2") (pintype "passive"))
    )
    (net (code "67") (name "/EEM_IO.LVDS_P5") (class "Default")
      (node (ref "J18") (pin "17") (pinfunction "17_17") (pintype "bidirectional"))
      (node (ref "R294") (pin "2") (pinfunction "2_2") (pintype "passive"))
    )
    (net (code "68") (name "/EEM_IO.LVDS_P6") (class "Default")
      (node (ref "J18") (pin "20") (pinfunction "20_20") (pintype "bidirectional"))
      (node (ref "R295") (pin "2") (pinfunction "2_2") (pintype "passive"))
    )
    (net (code "69") (name "/EEM_IO.LVDS_P7") (class "Default")
      (node (ref "J18") (pin "23") (pinfunction "23_23") (pintype "bidirectional"))
      (node (ref "R296") (pin "2") (pinfunction "2_2") (pintype "passive"))
    )
    (net (code "70") (name "/EEM_IO.LVDS_P8") (class "Default")
      (node (ref "J19") (pin "2") (pinfunction "2_2") (pintype "bidirectional"))
      (node (ref "R83") (pin "2") (pinfunction "2_2") (pintype "passive"))
    )
    (net (code "71") (name "/EEM_IO.LVDS_P9") (class "Default")
      (node (ref "J19") (pin "5") (pinfunction "5_5") (pintype "bidirectional"))
      (node (ref "R85") (pin "2") (pinfunction "2_2") (pintype "passive"))
    )
    (net (code "72") (name "/EEM_IO.LVDS_P10") (class "Default")
      (node (ref "J19") (pin "8") (pinfunction "8_8") (pintype "bidirectional"))
      (node (ref "R89") (pin "2") (pinfunction "2_2") (pintype "passive"))
    )
    (net (code "73") (name "/EEM_IO.LVDS_P11") (class "Default")
      (node (ref "J19") (pin "11") (pinfunction "11_11") (pintype "bidirectional"))
      (node (ref "R156") (pin "2") (pinfunction "2_2") (pintype "passive"))
    )
    (net (code "74") (name "/EEM_IO.LVDS_P12") (class "Default")
      (node (ref "J19") (pin "14") (pinfunction "14_14") (pintype "bidirectional"))
      (node (ref "R297") (pin "2") (pinfunction "2_2") (pintype "passive"))
    )
    (net (code "75") (name "/EEM_IO.LVDS_P13") (class "Default")
      (node (ref "J19") (pin "17") (pinfunction "17_17") (pintype "bidirectional"))
      (node (ref "R298") (pin "2") (pinfunction "2_2") (pintype "passive"))
    )
    (net (code "76") (name "/EEM_IO.LVDS_P14") (class "Default")
      (node (ref "J19") (pin "20") (pinfunction "20_20") (pintype "bidirectional"))
      (node (ref "R299") (pin "2") (pinfunction "2_2") (pintype "passive"))
    )
    (net (code "77") (name "/EEM_IO.LVDS_P15") (class "Default")
      (node (ref "J19") (pin "23") (pinfunction "23_23") (pintype "bidirectional"))
      (node (ref "R143") (pin "2") (pinfunction "2_2") (pintype "passive"))
    )
    (net (code "80") (name "/I2C_SCL1") (class "Default")
      (node (ref "D8") (pin "6") (pinfunction "C_6") (pintype "passive"))
      (node (ref "IC26") (pin "6") (pinfunction "SCL_6") (pintype "input"))
      (node (ref "IC43") (pin "1") (pinfunction "SCL_1") (pintype "input"))
      (node (ref "J19") (pin "27") (pinfunction "27_27") (pintype "bidirectional"))
      (node (ref "T5") (pin "3") (pinfunction "D_3") (pintype "passive"))
    )
    (net (code "81") (name "/I2C_SDA1") (class "Default")
      (node (ref "D8") (pin "4") (pinfunction "C_4") (pintype "passive"))
      (node (ref "IC26") (pin "5") (pinfunction "SDA_5") (pintype "bidirectional"))
      (node (ref "IC43") (pin "3") (pinfunction "SDA_3") (pintype "bidirectional"))
      (node (ref "J19") (pin "26") (pinfunction "26_26") (pintype "bidirectional"))
      (node (ref "T6") (pin "3") (pinfunction "D_3") (pintype "passive"))
    )
    (net (code "82") (name "/SERVMOD_3V3") (class "Default")
      (node (ref "IC40") (pin "13") (pinfunction "E_13") (pintype "input"))
      (node (ref "IC40") (pin "5") (pinfunction "E_5") (pintype "input"))
    )
    (net (code "83") (name "/Switch_I2C.SCL") (class "Default")
      (node (ref "IC40") (pin "2") (pinfunction "Z_2") (pintype "bidirectional"))
      (node (ref "R288") (pin "2") (pinfunction "2_2") (pintype "passive"))
    )
    (net (code "84") (name "/Switch_I2C.SDA") (class "Default")
      (node (ref "IC40") (pin "3") (pinfunction "Z_3") (pintype "bidirectional"))
      (node (ref "R287") (pin "2") (pinfunction "2_2") (pintype "passive"))
    )
    (net (code "86") (name "GND") (class "Default")
      (node (ref "C219") (pin "1") (pinfunction "1_1") (pintype "passive"))
      (node (ref "C220") (pin "1") (pinfunction "1_1") (pintype "passive"))
      (node (ref "C298") (pin "1") (pinfunction "1_1") (pintype "passive"))
      (node (ref "C306") (pin "1") (pinfunction "1_1") (pintype "passive"))
      (node (ref "C307") (pin "1") (pinfunction "1_1") (pintype "passive"))
      (node (ref "D8") (pin "2") (pinfunction "A_2") (pintype "passive"))
      (node (ref "IC25") (pin "1") (pinfunction "A0_1") (pintype "input"))
      (node (ref "IC25") (pin "2") (pinfunction "A1_2") (pintype "input"))
      (node (ref "IC25") (pin "3") (pinfunction "A2_3") (pintype "input"))
      (node (ref "IC25") (pin "4") (pinfunction "VSS_4") (pintype "power_in"))
      (node (ref "IC26") (pin "1") (pinfunction "A0_1") (pintype "input"))
      (node (ref "IC26") (pin "2") (pinfunction "A1_2") (pintype "input"))
      (node (ref "IC26") (pin "3") (pinfunction "A2_3") (pintype "input"))
      (node (ref "IC26") (pin "4") (pinfunction "VSS_4") (pintype "power_in"))
      (node (ref "IC40") (pin "10") (pinfunction "Z_10") (pintype "bidirectional"))
      (node (ref "IC40") (pin "11") (pinfunction "Y_11") (pintype "bidirectional"))
      (node (ref "IC40") (pin "12") (pinfunction "E_12") (pintype "input"))
      (node (ref "IC40") (pin "6") (pinfunction "E_6") (pintype "input"))
      (node (ref "IC40") (pin "7") (pinfunction "GND_7") (pintype "power_in"))
      (node (ref "IC40") (pin "8") (pinfunction "Y_8") (pintype "bidirectional"))
      (node (ref "IC40") (pin "9") (pinfunction "Z_9") (pintype "bidirectional"))
      (node (ref "IC42") (pin "2") (pinfunction "VSS_2") (pintype "power_in"))
      (node (ref "IC43") (pin "2") (pinfunction "VSS_2") (pintype "power_in"))
      (node (ref "J18") (pin "1") (pinfunction "1_1") (pintype "bidirectional"))
      (node (ref "J18") (pin "10") (pinfunction "10_10") (pintype "bidirectional"))
      (node (ref "J18") (pin "13") (pinfunction "13_13") (pintype "bidirectional"))
      (node (ref "J18") (pin "16") (pinfunction "16_16") (pintype "bidirectional"))
      (node (ref "J18") (pin "19") (pinfunction "19_19") (pintype "bidirectional"))
      (node (ref "J18") (pin "22") (pinfunction "22_22") (pintype "bidirectional"))
      (node (ref "J18") (pin "25") (pinfunction "25_25") (pintype "bidirectional"))
      (node (ref "J18") (pin "4") (pinfunction "4_4") (pintype "bidirectional"))
      (node (ref "J18") (pin "7") (pinfunction "7_7") (pintype "bidirectional"))
      (node (ref "J19") (pin "1") (pinfunction "1_1") (pintype "bidirectional"))
      (node (ref "J19") (pin "10") (pinfunction "10_10") (pintype "bidirectional"))
      (node (ref "J19") (pin "13") (pinfunction "13_13") (pintype "bidirectional"))
      (node (ref "J19") (pin "16") (pinfunction "16_16") (pintype "bidirectional"))
      (node (ref "J19") (pin "19") (pinfunction "19_19") (pintype "bidirectional"))
      (node (ref "J19") (pin "22") (pinfunction "22_22") (pintype "bidirectional"))
      (node (ref "J19") (pin "25") (pinfunction "25_25") (pintype "bidirectional"))
      (node (ref "J19") (pin "4") (pinfunction "4_4") (pintype "bidirectional"))
      (node (ref "J19") (pin "7") (pinfunction "7_7") (pintype "bidirectional"))
    )
    (net (code "87") (name "Net-(T3-G)") (class "Default")
      (node (ref "R96") (pin "1") (pinfunction "1_1") (pintype "passive"))
      (node (ref "T3") (pin "1") (pinfunction "G_1") (pintype "passive"))
    )
    (net (code "88") (name "Net-(T3-S)") (class "Default")
      (node (ref "R106") (pin "2") (pinfunction "2_2") (pintype "passive"))
      (node (ref "T3") (pin "2") (pinfunction "S_2") (pintype "passive"))
    )
    (net (code "89") (name "Net-(T4-G)") (class "Default")
      (node (ref "R86") (pin "1") (pinfunction "1_1") (pintype "passive"))
      (node (ref "T4") (pin "1") (pinfunction "G_1") (pintype "passive"))
    )
    (net (code "90") (name "Net-(T4-S)") (class "Default")
      (node (ref "R111") (pin "2") (pinfunction "2_2") (pintype "passive"))
      (node (ref "T4") (pin "2") (pinfunction "S_2") (pintype "passive"))
    )
    (net (code "91") (name "Net-(T5-G)") (class "Default")
      (node (ref "R115") (pin "1") (pinfunction "1_1") (pintype "passive"))
      (node (ref "T5") (pin "1") (pinfunction "G_1") (pintype "passive"))
    )
    (net (code "92") (name "Net-(T5-S)") (class "Default")
      (node (ref "R110") (pin "2") (pinfunction "2_2") (pintype "passive"))
      (node (ref "T5") (pin "2") (pinfunction "S_2") (pintype "passive"))
    )
    (net (code "93") (name "Net-(T6-G)") (class "Default")
      (node (ref "R116") (pin "1") (pinfunction "1_1") (pintype "passive"))
      (node (ref "T6") (pin "1") (pinfunction "G_1") (pintype "passive"))
    )
    (net (code "94") (name "Net-(T6-S)") (class "Default")
      (node (ref "R120") (pin "2") (pinfunction "2_2") (pintype "passive"))
      (node (ref "T6") (pin "2") (pinfunction "S_2") (pintype "passive"))
    )
    (net (code "95") (name "P3V3") (class "Default")
      (node (ref "C298") (pin "2") (pinfunction "2_2") (pintype "passive"))
      (node (ref "IC40") (pin "14") (pinfunction "VCC_14") (pintype "power_in"))
      (node (ref "R106") (pin "1") (pinfunction "1_1") (pintype "passive"))
      (node (ref "R110") (pin "1") (pinfunction "1_1") (pintype "passive"))
      (node (ref "R111") (pin "1") (pinfunction "1_1") (pintype "passive"))
      (node (ref "R115") (pin "2") (pinfunction "2_2") (pintype "passive"))
      (node (ref "R116") (pin "2") (pinfunction "2_2") (pintype "passive"))
      (node (ref "R120") (pin "1") (pinfunction "1_1") (pintype "passive"))
      (node (ref "R86") (pin "2") (pinfunction "2_2") (pintype "passive"))
      (node (ref "R96") (pin "2") (pinfunction "2_2") (pintype "passive"))
    )
    (net (code "96") (name "P3V3_MP") (class "Default")
      (node (ref "C219") (pin "2") (pinfunction "2_2") (pintype "passive"))
      (node (ref "C306") (pin "2") (pinfunction "2_2") (pintype "passive"))
      (node (ref "IC25") (pin "8") (pinfunction "VCC_8") (pintype "power_in"))
      (node (ref "IC42") (pin "4") (pinfunction "VCC_4") (pintype "power_in"))
      (node (ref "J18") (pin "30") (pinfunction "30_30") (pintype "bidirectional"))
    )
    (net (code "97") (name "P3V3_MP2") (class "Default")
      (node (ref "C220") (pin "2") (pinfunction "2_2") (pintype "passive"))
      (node (ref "C307") (pin "2") (pinfunction "2_2") (pintype "passive"))
      (node (ref "IC26") (pin "8") (pinfunction "VCC_8") (pintype "power_in"))
      (node (ref "IC43") (pin "4") (pinfunction "VCC_4") (pintype "power_in"))
      (node (ref "J19") (pin "30") (pinfunction "30_30") (pintype "bidirectional"))
    )
    (net (code "98") (name "P12V0") (class "Default")
      (node (ref "J18") (pin "28") (pinfunction "28_28") (pintype "bidirectional"))
      (node (ref "J18") (pin "29") (pinfunction "29_29") (pintype "bidirectional"))
      (node (ref "J19") (pin "28") (pinfunction "28_28") (pintype "bidirectional"))
      (node (ref "J19") (pin "29") (pinfunction "29_29") (pintype "bidirectional"))
      (node (ref "R257") (pin "2") (pinfunction "2_2") (pintype "passive"))
      (node (ref "R260") (pin "2") (pinfunction "2_2") (pintype "passive"))
      (node (ref "R261") (pin "2") (pinfunction "2_2") (pintype "passive"))
      (node (ref "R262") (pin "2") (pinfunction "2_2") (pintype "passive"))
    )
    (net (code "99") (name "P12V0_DIOT") (class "Default")
      (node (ref "R257") (pin "1") (pinfunction "1_1") (pintype "passive"))
      (node (ref "R260") (pin "1") (pinfunction "1_1") (pintype "passive"))
      (node (ref "R261") (pin "1") (pinfunction "1_1") (pintype "passive"))
      (node (ref "R262") (pin "1") (pinfunction "1_1") (pintype "passive"))
    )
    (net (code "100") (name "unconnected-(D8D-C-Pad5)") (class "Default")
      (node (ref "D8") (pin "5") (pinfunction "C_5") (pintype "passive+no_connect"))
    )
    (net (code "101") (name "unconnected-(IC25-NC-Pad7)") (class "Default")
      (node (ref "IC25") (pin "7") (pinfunction "NC_7") (pintype "passive+no_connect"))
    )
    (net (code "102") (name "unconnected-(IC26-NC-Pad7)") (class "Default")
      (node (ref "IC26") (pin "7") (pinfunction "NC_7") (pintype "passive+no_connect"))
    )
    (net (code "103") (name "unconnected-(IC42-NC-Pad5)") (class "Default")
      (node (ref "IC42") (pin "5") (pinfunction "NC_5") (pintype "passive+no_connect"))
    )
    (net (code "104") (name "unconnected-(IC43-NC-Pad5)") (class "Default")
      (node (ref "IC43") (pin "5") (pinfunction "NC_5") (pintype "passive+no_connect"))
    )
  )
)
